# Adafruit_PN532_Breakout_v1_6.net
KiCad netlist of a schematic drawn in EAGLE
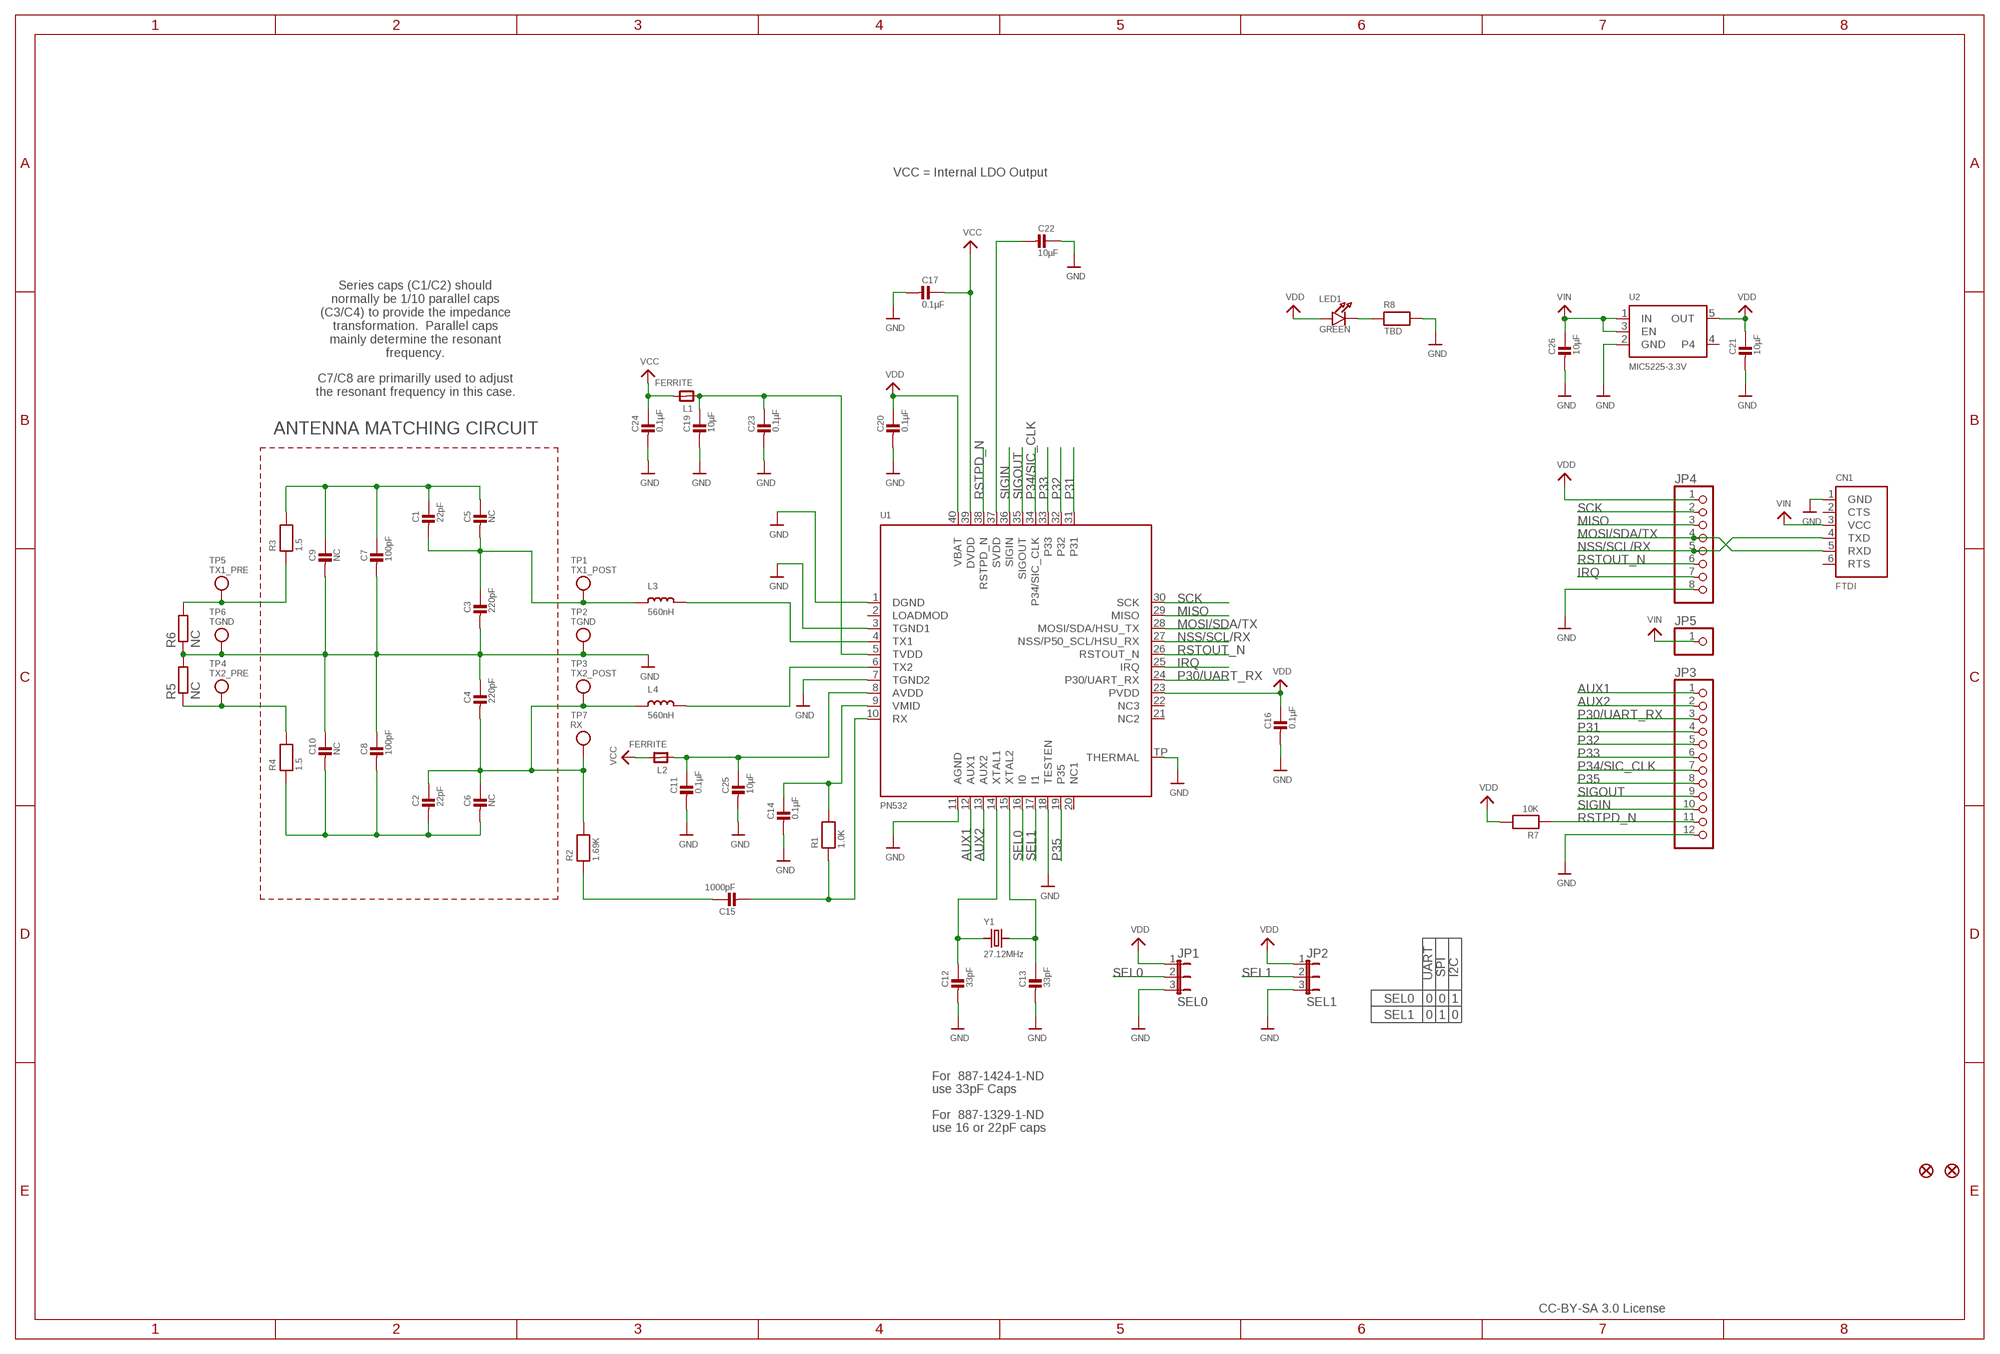
[diagram p0: schematic, sheet 1]

(export (version "E")
  (design (tool "Eeschema 10.0.6"))
  (components
    (comp (ref "C1")
      (value "22pF")
      (footprint "eagle-import:0805-NO")
      (libsource (lib "eagle-import") (part "CAP_CERAMIC0805-NOOUTLINE"))
    )
    (comp (ref "C2")
      (value "22pF")
      (footprint "eagle-import:0805-NO")
      (libsource (lib "eagle-import") (part "CAP_CERAMIC0805-NOOUTLINE"))
    )
    (comp (ref "C3")
      (value "220pF")
      (footprint "eagle-import:0805-NO")
      (libsource (lib "eagle-import") (part "CAP_CERAMIC0805-NOOUTLINE"))
    )
    (comp (ref "C4")
      (value "220pF")
      (footprint "eagle-import:0805-NO")
      (libsource (lib "eagle-import") (part "CAP_CERAMIC0805-NOOUTLINE"))
    )
    (comp (ref "C5")
      (value "NC")
      (footprint "eagle-import:0805-NO")
      (libsource (lib "eagle-import") (part "CAP_CERAMIC0805-NOOUTLINE"))
    )
    (comp (ref "C6")
      (value "NC")
      (footprint "eagle-import:0805-NO")
      (libsource (lib "eagle-import") (part "CAP_CERAMIC0805-NOOUTLINE"))
    )
    (comp (ref "C7")
      (value "100pF")
      (footprint "eagle-import:0805-NO")
      (libsource (lib "eagle-import") (part "CAP_CERAMIC0805-NOOUTLINE"))
    )
    (comp (ref "C8")
      (value "100pF")
      (footprint "eagle-import:0805-NO")
      (libsource (lib "eagle-import") (part "CAP_CERAMIC0805-NOOUTLINE"))
    )
    (comp (ref "C9")
      (value "NC")
      (footprint "eagle-import:0805-NO")
      (libsource (lib "eagle-import") (part "CAP_CERAMIC0805-NOOUTLINE"))
    )
    (comp (ref "C10")
      (value "NC")
      (footprint "eagle-import:0805-NO")
      (libsource (lib "eagle-import") (part "CAP_CERAMIC0805-NOOUTLINE"))
    )
    (comp (ref "C11")
      (value "0.1µF")
      (footprint "eagle-import:0805-NO")
      (libsource (lib "eagle-import") (part "CAP_CERAMIC0805-NOOUTLINE"))
    )
    (comp (ref "C12")
      (value "33pF")
      (footprint "eagle-import:0805-NO")
      (libsource (lib "eagle-import") (part "CAP_CERAMIC0805-NOOUTLINE"))
    )
    (comp (ref "C13")
      (value "33pF")
      (footprint "eagle-import:0805-NO")
      (libsource (lib "eagle-import") (part "CAP_CERAMIC0805-NOOUTLINE"))
    )
    (comp (ref "C14")
      (value "0.1µF")
      (footprint "eagle-import:0805-NO")
      (libsource (lib "eagle-import") (part "CAP_CERAMIC0805-NOOUTLINE"))
    )
    (comp (ref "C15")
      (value "1000pF")
      (footprint "eagle-import:0805-NO")
      (libsource (lib "eagle-import") (part "CAP_CERAMIC0805-NOOUTLINE"))
    )
    (comp (ref "C16")
      (value "0.1µF")
      (footprint "eagle-import:0805-NO")
      (libsource (lib "eagle-import") (part "CAP_CERAMIC0805-NOOUTLINE"))
    )
    (comp (ref "C17")
      (value "0.1µF")
      (footprint "eagle-import:0805-NO")
      (libsource (lib "eagle-import") (part "CAP_CERAMIC0805-NOOUTLINE"))
    )
    (comp (ref "C19")
      (value "10µF")
      (footprint "eagle-import:0805-NO")
      (libsource (lib "eagle-import") (part "CAP_CERAMIC0805-NOOUTLINE"))
    )
    (comp (ref "C20")
      (value "0.1µF")
      (footprint "eagle-import:0805-NO")
      (libsource (lib "eagle-import") (part "CAP_CERAMIC0805-NOOUTLINE"))
    )
    (comp (ref "C21")
      (value "10µF")
      (footprint "eagle-import:0805-NO")
      (libsource (lib "eagle-import") (part "CAP_CERAMIC0805-NOOUTLINE"))
    )
    (comp (ref "C22")
      (value "10µF")
      (footprint "eagle-import:0805-NO")
      (libsource (lib "eagle-import") (part "CAP_CERAMIC0805-NOOUTLINE"))
    )
    (comp (ref "C23")
      (value "0.1µF")
      (footprint "eagle-import:0805-NO")
      (libsource (lib "eagle-import") (part "CAP_CERAMIC0805-NOOUTLINE"))
    )
    (comp (ref "C24")
      (value "0.1µF")
      (footprint "eagle-import:0805-NO")
      (libsource (lib "eagle-import") (part "CAP_CERAMIC0805-NOOUTLINE"))
    )
    (comp (ref "C25")
      (value "10µF")
      (footprint "eagle-import:0805-NO")
      (libsource (lib "eagle-import") (part "CAP_CERAMIC0805-NOOUTLINE"))
    )
    (comp (ref "C26")
      (value "10µF")
      (footprint "eagle-import:0805-NO")
      (libsource (lib "eagle-import") (part "CAP_CERAMIC0805-NOOUTLINE"))
    )
    (comp (ref "CN1")
      (value "FTDI")
      (footprint "eagle-import:1X06_ROUND")
      (libsource (lib "eagle-import") (part "FTDIUSBCABLE"))
    )
    (comp (ref "FID1")
      (value "FIDUCIAL1X2.5")
      (footprint "eagle-import:FIDUCIAL-1X2.5")
      (libsource (lib "eagle-import") (part "FIDUCIAL1X2.5"))
    )
    (comp (ref "FID2")
      (value "FIDUCIAL1X2.5")
      (footprint "eagle-import:FIDUCIAL-1X2.5")
      (libsource (lib "eagle-import") (part "FIDUCIAL1X2.5"))
    )
    (comp (ref "JP1")
      (value "SEL0")
      (footprint "eagle-import:JUMPER3")
      (libsource (lib "eagle-import") (part "JUMPER3"))
    )
    (comp (ref "JP2")
      (value "SEL1")
      (footprint "eagle-import:JUMPER3")
      (libsource (lib "eagle-import") (part "JUMPER3"))
    )
    (comp (ref "JP3")
      (value "HEADER-1X12")
      (footprint "eagle-import:1X12_ROUND")
      (libsource (lib "eagle-import") (part "HEADER-1X12"))
    )
    (comp (ref "JP4")
      (value "HEADER-1X8ROUND")
      (footprint "eagle-import:1X08_ROUND")
      (libsource (lib "eagle-import") (part "HEADER-1X8ROUND"))
    )
    (comp (ref "JP5")
      (value "HEADER-1X1ROUND")
      (footprint "eagle-import:1X01_ROUND")
      (libsource (lib "eagle-import") (part "HEADER-1X1ROUND"))
    )
    (comp (ref "L1")
      (value "FERRITE")
      (footprint "eagle-import:0805")
      (libsource (lib "eagle-import") (part "FERRITE0805"))
    )
    (comp (ref "L2")
      (value "FERRITE")
      (footprint "eagle-import:0805")
      (libsource (lib "eagle-import") (part "FERRITE0805"))
    )
    (comp (ref "L3")
      (value "560nH")
      (footprint "eagle-import:0805")
      (libsource (lib "eagle-import") (part "INDUCTOR0805"))
    )
    (comp (ref "L4")
      (value "560nH")
      (footprint "eagle-import:0805")
      (libsource (lib "eagle-import") (part "INDUCTOR0805"))
    )
    (comp (ref "LED1")
      (value "GREEN")
      (footprint "eagle-import:CHIPLED_0805_NOOUTLINE")
      (libsource (lib "eagle-import") (part "LED0805_NOOUTLINE"))
    )
    (comp (ref "R1")
      (value "1.0K")
      (footprint "eagle-import:0805-NO")
      (libsource (lib "eagle-import") (part "RESISTOR0805_NOOUTLINE"))
    )
    (comp (ref "R2")
      (value "1.69K")
      (footprint "eagle-import:0805-NO")
      (libsource (lib "eagle-import") (part "RESISTOR0805_NOOUTLINE"))
    )
    (comp (ref "R3")
      (value "1.5")
      (footprint "eagle-import:0805-NO")
      (libsource (lib "eagle-import") (part "RESISTOR0805_NOOUTLINE"))
    )
    (comp (ref "R4")
      (value "1.5")
      (footprint "eagle-import:0805-NO")
      (libsource (lib "eagle-import") (part "RESISTOR0805_NOOUTLINE"))
    )
    (comp (ref "R5")
      (value "NC")
      (footprint "eagle-import:R0201")
      (libsource (lib "eagle-import") (part "R-EU_R0201"))
    )
    (comp (ref "R6")
      (value "NC")
      (footprint "eagle-import:R0201")
      (libsource (lib "eagle-import") (part "R-EU_R0201"))
    )
    (comp (ref "R7")
      (value "10K")
      (footprint "eagle-import:0805-NO")
      (libsource (lib "eagle-import") (part "RESISTOR0805_NOOUTLINE"))
    )
    (comp (ref "R8")
      (value "TBD")
      (footprint "eagle-import:0805-NO")
      (libsource (lib "eagle-import") (part "RESISTOR0805_NOOUTLINE"))
    )
    (comp (ref "TP1")
      (value "TX1_POST")
      (footprint "eagle-import:TESTPOINT_ROUND_1MM")
      (libsource (lib "eagle-import") (part "TESTPOINTROUND1MM"))
    )
    (comp (ref "TP2")
      (value "TGND")
      (footprint "eagle-import:TESTPOINT_ROUND_1MM")
      (libsource (lib "eagle-import") (part "TESTPOINTROUND1MM"))
    )
    (comp (ref "TP3")
      (value "TX2_POST")
      (footprint "eagle-import:TESTPOINT_ROUND_1MM")
      (libsource (lib "eagle-import") (part "TESTPOINTROUND1MM"))
    )
    (comp (ref "TP4")
      (value "TX2_PRE")
      (footprint "eagle-import:TESTPOINT_ROUND_1MM")
      (libsource (lib "eagle-import") (part "TESTPOINTROUND1MM"))
    )
    (comp (ref "TP5")
      (value "TX1_PRE")
      (footprint "eagle-import:TESTPOINT_ROUND_1MM")
      (libsource (lib "eagle-import") (part "TESTPOINTROUND1MM"))
    )
    (comp (ref "TP6")
      (value "TGND")
      (footprint "eagle-import:TESTPOINT_ROUND_1MM")
      (libsource (lib "eagle-import") (part "TESTPOINTROUND1MM"))
    )
    (comp (ref "TP7")
      (value "RX")
      (footprint "eagle-import:TESTPOINT_ROUND_1MM")
      (libsource (lib "eagle-import") (part "TESTPOINTROUND1MM"))
    )
    (comp (ref "U1")
      (value "PN532")
      (footprint "eagle-import:HVQFN40-6X6")
      (libsource (lib "eagle-import") (part "PN532"))
    )
    (comp (ref "U2")
      (value "MIC5225-3.3V")
      (footprint "eagle-import:SOT23-5")
      (libsource (lib "eagle-import") (part "VREG_SOT23-5"))
    )
    (comp (ref "Y1")
      (value "27.12MHz")
      (footprint "eagle-import:CRYSTAL_3.2X2.5")
      (libsource (lib "eagle-import") (part "CRYSTAL3.2X2.5"))
    )
  )
  (nets
    (net (code "1") (name "/AUX1") (class "Default")
      (node (ref "JP3") (pin "1") (pinfunction "1_1") (pintype "passive"))
      (node (ref "U1") (pin "12") (pinfunction "AUX1_12") (pintype "bidirectional"))
    )
    (net (code "2") (name "/AUX2") (class "Default")
      (node (ref "JP3") (pin "2") (pinfunction "2_2") (pintype "passive"))
      (node (ref "U1") (pin "13") (pinfunction "AUX2_13") (pintype "bidirectional"))
    )
    (net (code "3") (name "/IRQ") (class "Default")
      (node (ref "JP4") (pin "7") (pinfunction "7_7") (pintype "passive"))
      (node (ref "U1") (pin "25") (pinfunction "IRQ_25") (pintype "bidirectional"))
    )
    (net (code "4") (name "/MISO") (class "Default")
      (node (ref "JP4") (pin "3") (pinfunction "3_3") (pintype "passive"))
      (node (ref "U1") (pin "29") (pinfunction "MISO_29") (pintype "bidirectional"))
    )
    (net (code "5") (name "/MOSI{slash}SDA{slash}TX") (class "Default")
      (node (ref "CN1") (pin "5") (pinfunction "RXD_5") (pintype "bidirectional"))
      (node (ref "JP4") (pin "4") (pinfunction "4_4") (pintype "passive"))
      (node (ref "U1") (pin "28") (pinfunction "MOSI/SDA/HSU_TX_28") (pintype "bidirectional"))
    )
    (net (code "6") (name "/NSS{slash}SCL{slash}RX") (class "Default")
      (node (ref "CN1") (pin "4") (pinfunction "TXD_4") (pintype "bidirectional"))
      (node (ref "JP4") (pin "5") (pinfunction "5_5") (pintype "passive"))
      (node (ref "U1") (pin "27") (pinfunction "NSS/P50_SCL/HSU_RX_27") (pintype "bidirectional"))
    )
    (net (code "7") (name "/P30{slash}UART_RX") (class "Default")
      (node (ref "JP3") (pin "3") (pinfunction "3_3") (pintype "passive"))
      (node (ref "U1") (pin "24") (pinfunction "P30/UART_RX_24") (pintype "bidirectional"))
    )
    (net (code "8") (name "/P31") (class "Default")
      (node (ref "JP3") (pin "4") (pinfunction "4_4") (pintype "passive"))
      (node (ref "U1") (pin "31") (pinfunction "P31_31") (pintype "bidirectional"))
    )
    (net (code "9") (name "/P32") (class "Default")
      (node (ref "JP3") (pin "5") (pinfunction "5_5") (pintype "passive"))
      (node (ref "U1") (pin "32") (pinfunction "P32_32") (pintype "bidirectional"))
    )
    (net (code "10") (name "/P33") (class "Default")
      (node (ref "JP3") (pin "6") (pinfunction "6_6") (pintype "passive"))
      (node (ref "U1") (pin "33") (pinfunction "P33_33") (pintype "bidirectional"))
    )
    (net (code "11") (name "/P34{slash}SIC_CLK") (class "Default")
      (node (ref "JP3") (pin "7") (pinfunction "7_7") (pintype "passive"))
      (node (ref "U1") (pin "34") (pinfunction "P34/SIC_CLK_34") (pintype "bidirectional"))
    )
    (net (code "12") (name "/P35") (class "Default")
      (node (ref "JP3") (pin "8") (pinfunction "8_8") (pintype "passive"))
      (node (ref "U1") (pin "19") (pinfunction "P35_19") (pintype "bidirectional"))
    )
    (net (code "13") (name "/RSTOUT_N") (class "Default")
      (node (ref "JP4") (pin "6") (pinfunction "6_6") (pintype "passive"))
      (node (ref "U1") (pin "26") (pinfunction "RSTOUT_N_26") (pintype "bidirectional"))
    )
    (net (code "14") (name "/RSTPD_N") (class "Default")
      (node (ref "JP3") (pin "11") (pinfunction "11_11") (pintype "passive"))
      (node (ref "R7") (pin "1") (pinfunction "1_1") (pintype "passive"))
      (node (ref "U1") (pin "38") (pinfunction "RSTPD_N_38") (pintype "bidirectional"))
    )
    (net (code "15") (name "/SCK") (class "Default")
      (node (ref "JP4") (pin "2") (pinfunction "2_2") (pintype "passive"))
      (node (ref "U1") (pin "30") (pinfunction "SCK_30") (pintype "bidirectional"))
    )
    (net (code "16") (name "/SEL0") (class "Default")
      (node (ref "JP1") (pin "2") (pinfunction "2_2") (pintype "passive"))
      (node (ref "U1") (pin "16") (pinfunction "I0_16") (pintype "bidirectional"))
    )
    (net (code "17") (name "/SEL1") (class "Default")
      (node (ref "JP2") (pin "2") (pinfunction "2_2") (pintype "passive"))
      (node (ref "U1") (pin "17") (pinfunction "I1_17") (pintype "bidirectional"))
    )
    (net (code "18") (name "/SIGIN") (class "Default")
      (node (ref "JP3") (pin "10") (pinfunction "10_10") (pintype "passive"))
      (node (ref "U1") (pin "36") (pinfunction "SIGIN_36") (pintype "bidirectional"))
    )
    (net (code "19") (name "/SIGOUT") (class "Default")
      (node (ref "JP3") (pin "9") (pinfunction "9_9") (pintype "passive"))
      (node (ref "U1") (pin "35") (pinfunction "SIGOUT_35") (pintype "bidirectional"))
    )
    (net (code "20") (name "GND") (class "Default")
      (node (ref "C10") (pin "1") (pinfunction "1_1") (pintype "passive"))
      (node (ref "C11") (pin "2") (pinfunction "2_2") (pintype "passive"))
      (node (ref "C12") (pin "2") (pinfunction "2_2") (pintype "passive"))
      (node (ref "C13") (pin "2") (pinfunction "2_2") (pintype "passive"))
      (node (ref "C14") (pin "2") (pinfunction "2_2") (pintype "passive"))
      (node (ref "C16") (pin "2") (pinfunction "2_2") (pintype "passive"))
      (node (ref "C17") (pin "2") (pinfunction "2_2") (pintype "passive"))
      (node (ref "C19") (pin "2") (pinfunction "2_2") (pintype "passive"))
      (node (ref "C20") (pin "2") (pinfunction "2_2") (pintype "passive"))
      (node (ref "C21") (pin "2") (pinfunction "2_2") (pintype "passive"))
      (node (ref "C22") (pin "1") (pinfunction "1_1") (pintype "passive"))
      (node (ref "C23") (pin "2") (pinfunction "2_2") (pintype "passive"))
      (node (ref "C24") (pin "2") (pinfunction "2_2") (pintype "passive"))
      (node (ref "C25") (pin "2") (pinfunction "2_2") (pintype "passive"))
      (node (ref "C26") (pin "2") (pinfunction "2_2") (pintype "passive"))
      (node (ref "C3") (pin "2") (pinfunction "2_2") (pintype "passive"))
      (node (ref "C4") (pin "1") (pinfunction "1_1") (pintype "passive"))
      (node (ref "C7") (pin "2") (pinfunction "2_2") (pintype "passive"))
      (node (ref "C8") (pin "1") (pinfunction "1_1") (pintype "passive"))
      (node (ref "C9") (pin "2") (pinfunction "2_2") (pintype "passive"))
      (node (ref "CN1") (pin "1") (pinfunction "GND_1") (pintype "bidirectional"))
      (node (ref "JP1") (pin "3") (pinfunction "3_3") (pintype "passive"))
      (node (ref "JP2") (pin "3") (pinfunction "3_3") (pintype "passive"))
      (node (ref "JP3") (pin "12") (pinfunction "12_12") (pintype "passive"))
      (node (ref "JP4") (pin "8") (pinfunction "8_8") (pintype "passive"))
      (node (ref "R5") (pin "2") (pinfunction "2_2") (pintype "passive"))
      (node (ref "R6") (pin "1") (pinfunction "1_1") (pintype "passive"))
      (node (ref "R8") (pin "2") (pinfunction "2_2") (pintype "passive"))
      (node (ref "TP2") (pin "P$1") (pinfunction "P$1_P$1") (pintype "bidirectional"))
      (node (ref "TP6") (pin "P$1") (pinfunction "P$1_P$1") (pintype "bidirectional"))
      (node (ref "U1") (pin "1") (pinfunction "DGND_1") (pintype "bidirectional"))
      (node (ref "U1") (pin "11") (pinfunction "AGND_11") (pintype "bidirectional"))
      (node (ref "U1") (pin "18") (pinfunction "TESTEN_18") (pintype "bidirectional"))
      (node (ref "U1") (pin "3") (pinfunction "TGND1_3") (pintype "bidirectional"))
      (node (ref "U1") (pin "7") (pinfunction "TGND2_7") (pintype "bidirectional"))
      (node (ref "U1") (pin "TP") (pinfunction "THERMAL_TP") (pintype "bidirectional"))
      (node (ref "U2") (pin "2") (pinfunction "GND_2") (pintype "power_in"))
    )
    (net (code "21") (name "Net-(C1-Pad1)") (class "Default")
      (node (ref "C1") (pin "1") (pinfunction "1_1") (pintype "passive"))
      (node (ref "C5") (pin "1") (pinfunction "1_1") (pintype "passive"))
      (node (ref "C7") (pin "1") (pinfunction "1_1") (pintype "passive"))
      (node (ref "C9") (pin "1") (pinfunction "1_1") (pintype "passive"))
      (node (ref "R3") (pin "2") (pinfunction "2_2") (pintype "passive"))
    )
    (net (code "22") (name "Net-(C1-Pad2)") (class "Default")
      (node (ref "C1") (pin "2") (pinfunction "2_2") (pintype "passive"))
      (node (ref "C3") (pin "1") (pinfunction "1_1") (pintype "passive"))
      (node (ref "C5") (pin "2") (pinfunction "2_2") (pintype "passive"))
      (node (ref "L3") (pin "1") (pinfunction "1_1") (pintype "passive"))
      (node (ref "TP1") (pin "P$1") (pinfunction "P$1_P$1") (pintype "bidirectional"))
    )
    (net (code "23") (name "Net-(C2-Pad1)") (class "Default")
      (node (ref "C2") (pin "1") (pinfunction "1_1") (pintype "passive"))
      (node (ref "C4") (pin "2") (pinfunction "2_2") (pintype "passive"))
      (node (ref "C6") (pin "1") (pinfunction "1_1") (pintype "passive"))
      (node (ref "L4") (pin "1") (pinfunction "1_1") (pintype "passive"))
      (node (ref "R2") (pin "2") (pinfunction "2_2") (pintype "passive"))
      (node (ref "TP3") (pin "P$1") (pinfunction "P$1_P$1") (pintype "bidirectional"))
      (node (ref "TP7") (pin "P$1") (pinfunction "P$1_P$1") (pintype "bidirectional"))
    )
    (net (code "24") (name "Net-(C10-Pad2)") (class "Default")
      (node (ref "C10") (pin "2") (pinfunction "2_2") (pintype "passive"))
      (node (ref "C2") (pin "2") (pinfunction "2_2") (pintype "passive"))
      (node (ref "C6") (pin "2") (pinfunction "2_2") (pintype "passive"))
      (node (ref "C8") (pin "2") (pinfunction "2_2") (pintype "passive"))
      (node (ref "R4") (pin "1") (pinfunction "1_1") (pintype "passive"))
    )
    (net (code "25") (name "Net-(C15-Pad1)") (class "Default")
      (node (ref "C15") (pin "1") (pinfunction "1_1") (pintype "passive"))
      (node (ref "R2") (pin "1") (pinfunction "1_1") (pintype "passive"))
    )
    (net (code "26") (name "Net-(L1-P$1)") (class "Default")
      (node (ref "C19") (pin "1") (pinfunction "1_1") (pintype "passive"))
      (node (ref "C23") (pin "1") (pinfunction "1_1") (pintype "passive"))
      (node (ref "L1") (pin "1") (pinfunction "P$1_1") (pintype "passive"))
      (node (ref "U1") (pin "5") (pinfunction "TVDD_5") (pintype "bidirectional"))
    )
    (net (code "27") (name "Net-(L2-P$1)") (class "Default")
      (node (ref "C11") (pin "1") (pinfunction "1_1") (pintype "passive"))
      (node (ref "C25") (pin "1") (pinfunction "1_1") (pintype "passive"))
      (node (ref "L2") (pin "1") (pinfunction "P$1_1") (pintype "passive"))
      (node (ref "U1") (pin "8") (pinfunction "AVDD_8") (pintype "bidirectional"))
    )
    (net (code "28") (name "Net-(LED1-PadC)") (class "Default")
      (node (ref "LED1") (pin "C") (pinfunction "C_C") (pintype "passive"))
      (node (ref "R8") (pin "1") (pinfunction "1_1") (pintype "passive"))
    )
    (net (code "29") (name "Net-(R3-Pad1)") (class "Default")
      (node (ref "R3") (pin "1") (pinfunction "1_1") (pintype "passive"))
      (node (ref "R6") (pin "2") (pinfunction "2_2") (pintype "passive"))
      (node (ref "TP5") (pin "P$1") (pinfunction "P$1_P$1") (pintype "bidirectional"))
    )
    (net (code "30") (name "Net-(R4-Pad2)") (class "Default")
      (node (ref "R4") (pin "2") (pinfunction "2_2") (pintype "passive"))
      (node (ref "R5") (pin "1") (pinfunction "1_1") (pintype "passive"))
      (node (ref "TP4") (pin "P$1") (pinfunction "P$1_P$1") (pintype "bidirectional"))
    )
    (net (code "31") (name "Net-(U1-RX)") (class "Default")
      (node (ref "C15") (pin "2") (pinfunction "2_2") (pintype "passive"))
      (node (ref "R1") (pin "1") (pinfunction "1_1") (pintype "passive"))
      (node (ref "U1") (pin "10") (pinfunction "RX_10") (pintype "bidirectional"))
    )
    (net (code "32") (name "Net-(U1-SVDD)") (class "Default")
      (node (ref "C22") (pin "2") (pinfunction "2_2") (pintype "passive"))
      (node (ref "U1") (pin "37") (pinfunction "SVDD_37") (pintype "bidirectional"))
    )
    (net (code "33") (name "Net-(U1-TX1)") (class "Default")
      (node (ref "L3") (pin "2") (pinfunction "2_2") (pintype "passive"))
      (node (ref "U1") (pin "4") (pinfunction "TX1_4") (pintype "bidirectional"))
    )
    (net (code "34") (name "Net-(U1-TX2)") (class "Default")
      (node (ref "L4") (pin "2") (pinfunction "2_2") (pintype "passive"))
      (node (ref "U1") (pin "6") (pinfunction "TX2_6") (pintype "bidirectional"))
    )
    (net (code "35") (name "Net-(U1-VMID)") (class "Default")
      (node (ref "C14") (pin "1") (pinfunction "1_1") (pintype "passive"))
      (node (ref "R1") (pin "2") (pinfunction "2_2") (pintype "passive"))
      (node (ref "U1") (pin "9") (pinfunction "VMID_9") (pintype "bidirectional"))
    )
    (net (code "36") (name "Net-(U1-XTAL1)") (class "Default")
      (node (ref "C12") (pin "1") (pinfunction "1_1") (pintype "passive"))
      (node (ref "U1") (pin "14") (pinfunction "XTAL1_14") (pintype "bidirectional"))
      (node (ref "Y1") (pin "1") (pinfunction "1_1") (pintype "passive"))
    )
    (net (code "37") (name "Net-(U1-XTAL2)") (class "Default")
      (node (ref "C13") (pin "1") (pinfunction "1_1") (pintype "passive"))
      (node (ref "U1") (pin "15") (pinfunction "XTAL2_15") (pintype "bidirectional"))
      (node (ref "Y1") (pin "2") (pinfunction "2_2") (pintype "passive"))
    )
    (net (code "38") (name "VCC") (class "Default")
      (node (ref "C17") (pin "1") (pinfunction "1_1") (pintype "passive"))
      (node (ref "C24") (pin "1") (pinfunction "1_1") (pintype "passive"))
      (node (ref "L1") (pin "2") (pinfunction "P$2_2") (pintype "passive"))
      (node (ref "L2") (pin "2") (pinfunction "P$2_2") (pintype "passive"))
      (node (ref "U1") (pin "39") (pinfunction "DVDD_39") (pintype "bidirectional"))
    )
    (net (code "39") (name "VDD") (class "Default")
      (node (ref "C16") (pin "1") (pinfunction "1_1") (pintype "passive"))
      (node (ref "C20") (pin "1") (pinfunction "1_1") (pintype "passive"))
      (node (ref "C21") (pin "1") (pinfunction "1_1") (pintype "passive"))
      (node (ref "JP1") (pin "1") (pinfunction "1_1") (pintype "passive"))
      (node (ref "JP2") (pin "1") (pinfunction "1_1") (pintype "passive"))
      (node (ref "JP4") (pin "1") (pinfunction "1_1") (pintype "passive"))
      (node (ref "LED1") (pin "A") (pinfunction "A_A") (pintype "passive"))
      (node (ref "R7") (pin "2") (pinfunction "2_2") (pintype "passive"))
      (node (ref "U1") (pin "23") (pinfunction "PVDD_23") (pintype "bidirectional"))
      (node (ref "U1") (pin "40") (pinfunction "VBAT_40") (pintype "bidirectional"))
      (node (ref "U2") (pin "5") (pinfunction "OUT_5") (pintype "power_in"))
    )
    (net (code "40") (name "VIN") (class "Default")
      (node (ref "C26") (pin "1") (pinfunction "1_1") (pintype "passive"))
      (node (ref "CN1") (pin "3") (pinfunction "VCC_3") (pintype "bidirectional"))
      (node (ref "JP5") (pin "1") (pinfunction "1_1") (pintype "passive"))
      (node (ref "U2") (pin "1") (pinfunction "IN_1") (pintype "power_in"))
      (node (ref "U2") (pin "3") (pinfunction "EN_3") (pintype "input"))
    )
    (net (code "41") (name "unconnected-(CN1-CTS-Pad2)") (class "Default")
      (node (ref "CN1") (pin "2") (pinfunction "CTS_2") (pintype "bidirectional"))
    )
    (net (code "42") (name "unconnected-(CN1-RTS-Pad6)") (class "Default")
      (node (ref "CN1") (pin "6") (pinfunction "RTS_6") (pintype "bidirectional"))
    )
    (net (code "43") (name "unconnected-(U1-LOADMOD-Pad2)") (class "Default")
      (node (ref "U1") (pin "2") (pinfunction "LOADMOD_2") (pintype "bidirectional"))
    )
    (net (code "44") (name "unconnected-(U1-NC1-Pad20)") (class "Default")
      (node (ref "U1") (pin "20") (pinfunction "NC1_20") (pintype "bidirectional"))
    )
    (net (code "45") (name "unconnected-(U1-NC2-Pad21)") (class "Default")
      (node (ref "U1") (pin "21") (pinfunction "NC2_21") (pintype "bidirectional"))
    )
    (net (code "46") (name "unconnected-(U1-NC3-Pad22)") (class "Default")
      (node (ref "U1") (pin "22") (pinfunction "NC3_22") (pintype "bidirectional"))
    )
    (net (code "47") (name "unconnected-(U2-P4-Pad4)") (class "Default")
      (node (ref "U2") (pin "4") (pinfunction "P4_4") (pintype "bidirectional"))
    )
  )
)
